# 05_-_MSP430F5529.net
KiCad netlist of a schematic drawn in Altium Designer
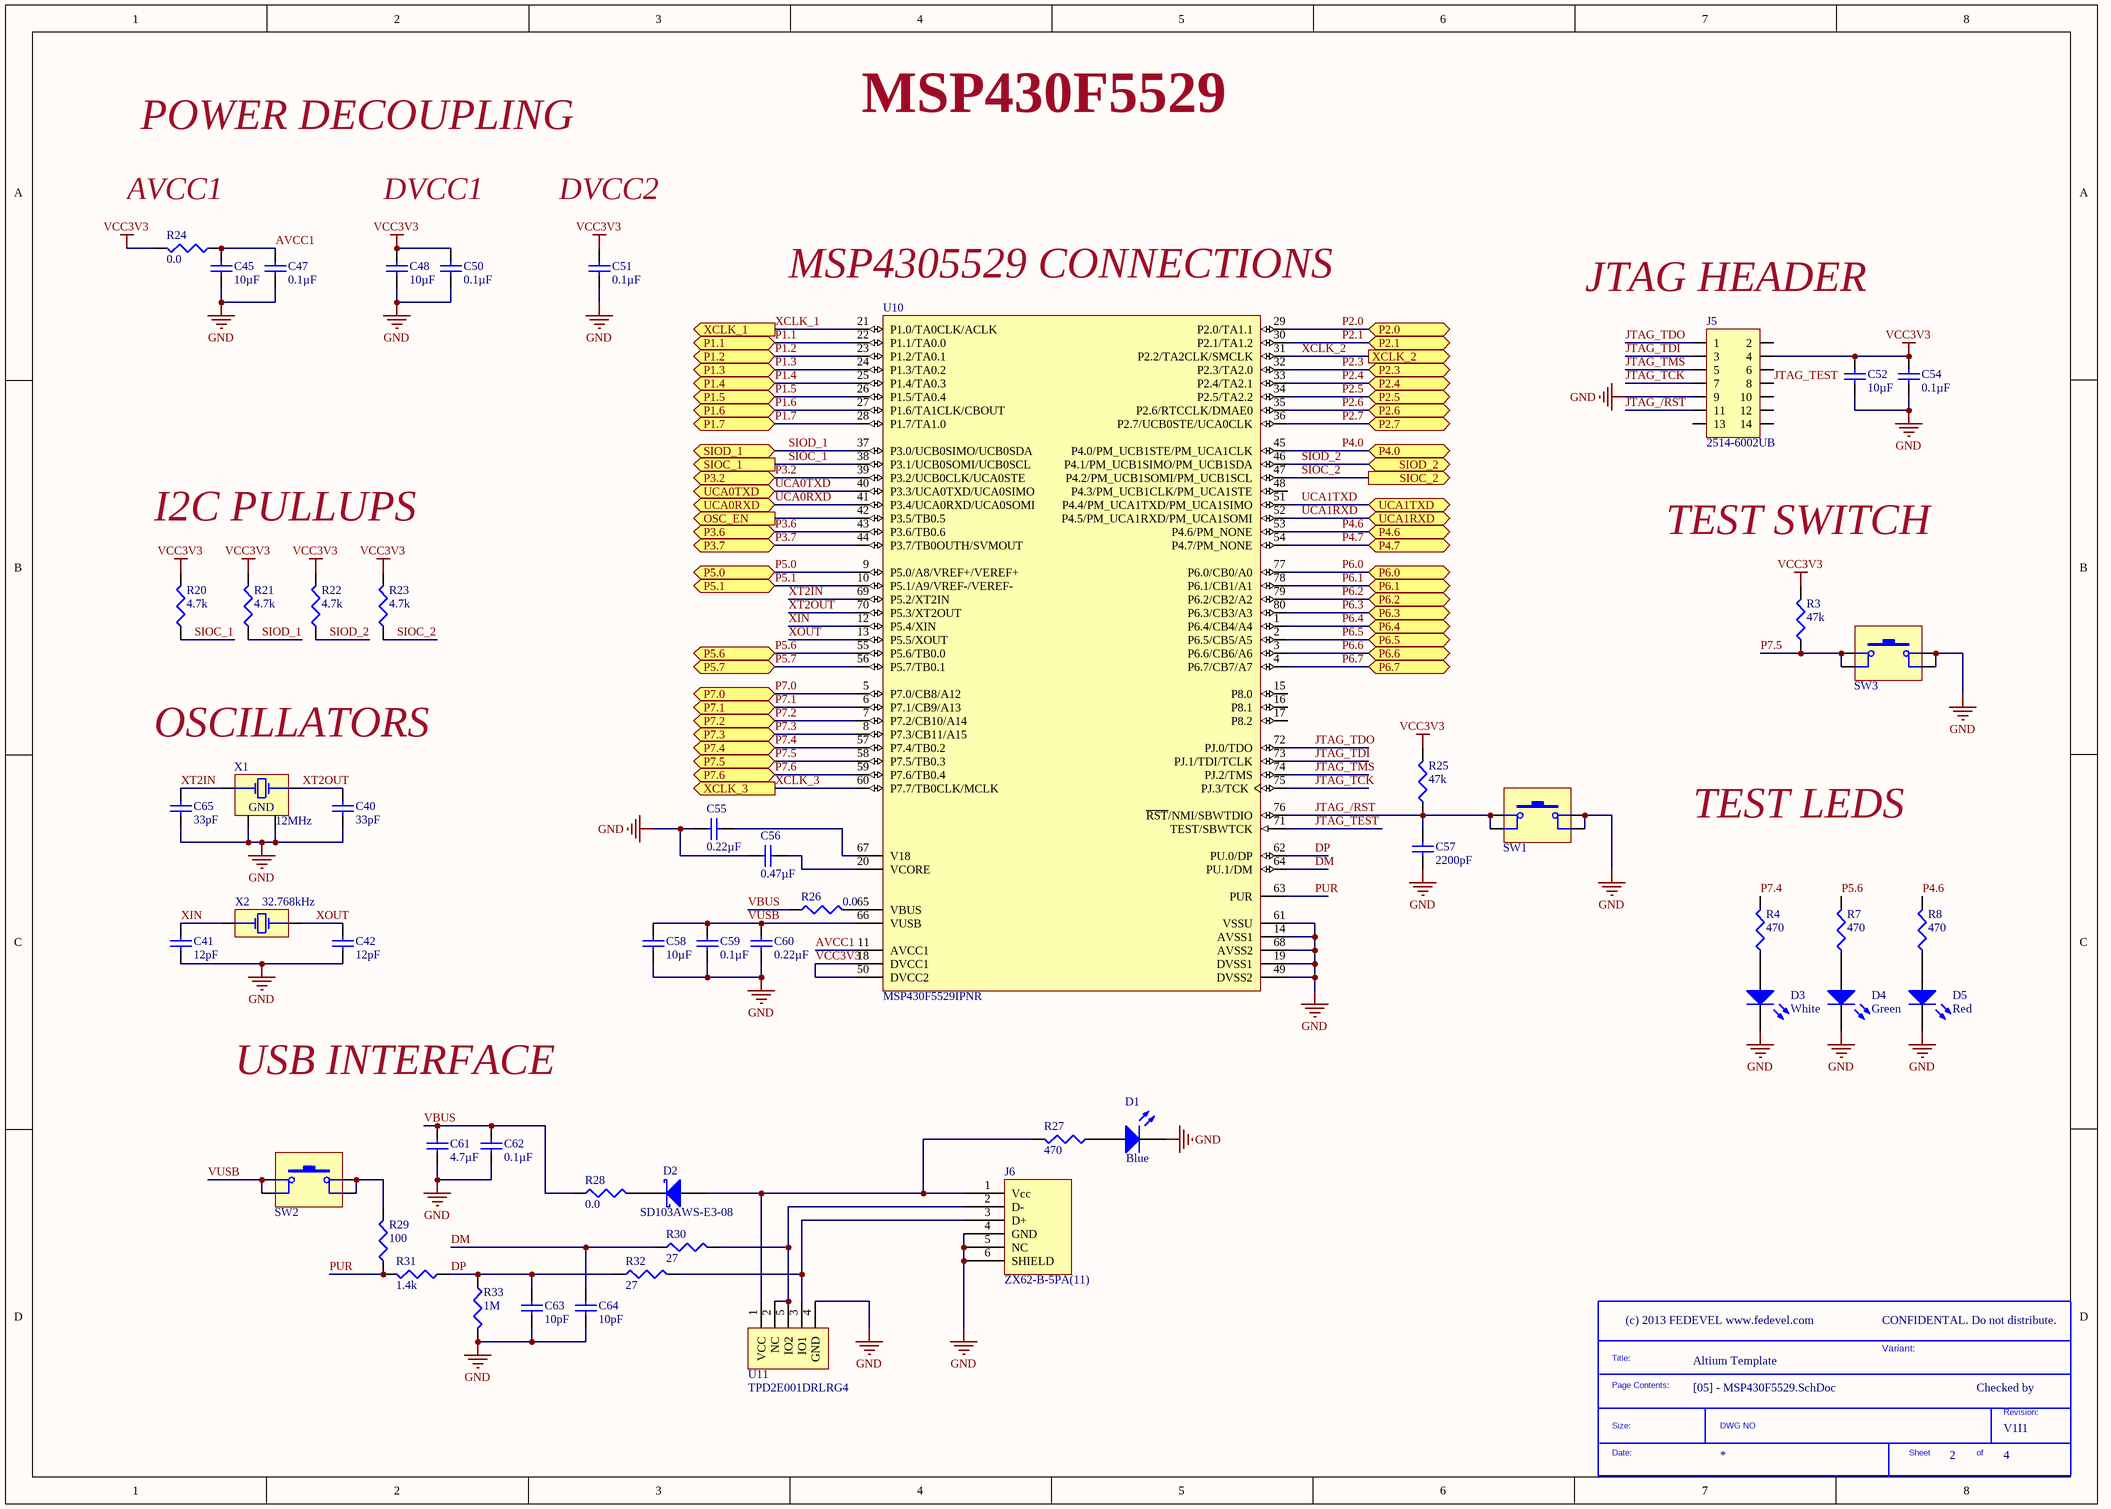
[diagram p0: [05] - MSP430F5529.SchDoc]

(export (version "E")
  (design (tool "Eeschema 10.0.6"))
  (components
    (comp (ref "C40")
      (value "C1608C0G1H330J080AA")
      (footprint "CAP-0603")
      (description "CAP CER 33PF 50V C0G 0603")
      (fields
        (field (name "MANUFACTURER") "TDK Corporation")
        (field (name "TOLERANCE") "±5%")
        (field (name "CAPACITANCE") "33pF")
      )
      (libsource (lib "camera_module") (part "C1608C0G1H330J080AA"))
    )
    (comp (ref "C41")
      (value "C1608C0G1H120J080AA")
      (footprint "CAP-0603")
      (description "CAP CER 12PF 50V C0G 0603")
      (fields
        (field (name "MANUFACTURER") "TDK Corporation")
        (field (name "TOLERANCE") "±5%")
        (field (name "CAPACITANCE") "12pF")
      )
      (libsource (lib "camera_module") (part "C1608C0G1H120J080AA"))
    )
    (comp (ref "C42")
      (value "C1608C0G1H120J080AA")
      (footprint "CAP-0603")
      (description "CAP CER 12PF 50V C0G 0603")
      (fields
        (field (name "MANUFACTURER") "TDK Corporation")
        (field (name "TOLERANCE") "±5%")
        (field (name "CAPACITANCE") "12pF")
      )
      (libsource (lib "camera_module") (part "C1608C0G1H120J080AA"))
    )
    (comp (ref "C45")
      (value "GRM21BR61E106KA73L")
      (footprint "CAP-0805")
      (description "CAP CER 10UF 25V X5R 0805")
      (fields
        (field (name "MANUFACTURER") "Murata Electronics North America")
        (field (name "TOLERANCE") "±10%")
        (field (name "CAPACITANCE") "10µF")
      )
      (libsource (lib "camera_module") (part "GRM21BR61E106KA73L"))
    )
    (comp (ref "C47")
      (value "GRM188R71C104KA01D")
      (footprint "CAP-0603")
      (description "CAP CER 0.1UF 16V X7R 0603")
      (fields
        (field (name "MANUFACTURER") "Murata Electronics North America")
        (field (name "TOLERANCE") "±10%")
        (field (name "CAPACITANCE") "0.1µF")
      )
      (libsource (lib "camera_module") (part "GRM188R71C104KA01D"))
    )
    (comp (ref "C48")
      (value "GRM21BR61E106KA73L")
      (footprint "CAP-0805")
      (description "CAP CER 10UF 25V X5R 0805")
      (fields
        (field (name "MANUFACTURER") "Murata Electronics North America")
        (field (name "TOLERANCE") "±10%")
        (field (name "CAPACITANCE") "10µF")
      )
      (libsource (lib "camera_module") (part "GRM21BR61E106KA73L"))
    )
    (comp (ref "C50")
      (value "GRM188R71C104KA01D")
      (footprint "CAP-0603")
      (description "CAP CER 0.1UF 16V X7R 0603")
      (fields
        (field (name "MANUFACTURER") "Murata Electronics North America")
        (field (name "TOLERANCE") "±10%")
        (field (name "CAPACITANCE") "0.1µF")
      )
      (libsource (lib "camera_module") (part "GRM188R71C104KA01D"))
    )
    (comp (ref "C51")
      (value "GRM188R71C104KA01D")
      (footprint "CAP-0603")
      (description "CAP CER 0.1UF 16V X7R 0603")
      (fields
        (field (name "MANUFACTURER") "Murata Electronics North America")
        (field (name "TOLERANCE") "±10%")
        (field (name "CAPACITANCE") "0.1µF")
      )
      (libsource (lib "camera_module") (part "GRM188R71C104KA01D"))
    )
    (comp (ref "C52")
      (value "GRM21BR61E106KA73L")
      (footprint "CAP-0805")
      (description "CAP CER 10UF 25V X5R 0805")
      (fields
        (field (name "MANUFACTURER") "Murata Electronics North America")
        (field (name "TOLERANCE") "±10%")
        (field (name "CAPACITANCE") "10µF")
      )
      (libsource (lib "camera_module") (part "GRM21BR61E106KA73L"))
    )
    (comp (ref "C54")
      (value "GRM188R71C104KA01D")
      (footprint "CAP-0603")
      (description "CAP CER 0.1UF 16V X7R 0603")
      (fields
        (field (name "MANUFACTURER") "Murata Electronics North America")
        (field (name "TOLERANCE") "±10%")
        (field (name "CAPACITANCE") "0.1µF")
      )
      (libsource (lib "camera_module") (part "GRM188R71C104KA01D"))
    )
    (comp (ref "C55")
      (value "GRM188R71C224KA01D")
      (footprint "CAP-0603")
      (description "CAP CER 0.22UF 16V X7R 0603")
      (fields
        (field (name "MANUFACTURER") "Murata Electronics North America")
        (field (name "TOLERANCE") "±10%")
        (field (name "CAPACITANCE") "0.22µF")
      )
      (libsource (lib "camera_module") (part "GRM188R71C224KA01D"))
    )
    (comp (ref "C56")
      (value "C1608X5R1C474K080AA")
      (footprint "CAP-0603")
      (description "CAP CER 0.47UF 16V X5R 0603")
      (fields
        (field (name "MANUFACTURER") "TDK Corporation")
        (field (name "TOLERANCE") "±10%")
        (field (name "CAPACITANCE") "0.47µF")
      )
      (libsource (lib "camera_module") (part "C1608X5R1C474K080AA"))
    )
    (comp (ref "C57")
      (value "GRM188R71C222KA01D")
      (footprint "CAP-0603")
      (description "CAP CER 2200PF 16V X7R 0603")
      (fields
        (field (name "MANUFACTURER") "Murata Electronics North America")
        (field (name "TOLERANCE") "±10%")
        (field (name "CAPACITANCE") "2200pF")
      )
      (libsource (lib "camera_module") (part "GRM188R71C222KA01D"))
    )
    (comp (ref "C58")
      (value "GRM21BR61E106KA73L")
      (footprint "CAP-0805")
      (description "CAP CER 10UF 25V X5R 0805")
      (fields
        (field (name "MANUFACTURER") "Murata Electronics North America")
        (field (name "TOLERANCE") "±10%")
        (field (name "CAPACITANCE") "10µF")
      )
      (libsource (lib "camera_module") (part "GRM21BR61E106KA73L"))
    )
    (comp (ref "C59")
      (value "GRM188R71C104KA01D")
      (footprint "CAP-0603")
      (description "CAP CER 0.1UF 16V X7R 0603")
      (fields
        (field (name "MANUFACTURER") "Murata Electronics North America")
        (field (name "TOLERANCE") "±10%")
        (field (name "CAPACITANCE") "0.1µF")
      )
      (libsource (lib "camera_module") (part "GRM188R71C104KA01D"))
    )
    (comp (ref "C60")
      (value "GRM188R71C224KA01D")
      (footprint "CAP-0603")
      (description "CAP CER 0.22UF 16V X7R 0603")
      (fields
        (field (name "MANUFACTURER") "Murata Electronics North America")
        (field (name "TOLERANCE") "±10%")
        (field (name "CAPACITANCE") "0.22µF")
      )
      (libsource (lib "camera_module") (part "GRM188R71C224KA01D"))
    )
    (comp (ref "C61")
      (value "GRM188R60J475KE19D")
      (footprint "CAP-0603")
      (description "CAP CER 4.7UF 6.3V X5R 0603")
      (fields
        (field (name "MANUFACTURER") "Murata Electronics North America")
        (field (name "TOLERANCE") "±10%")
        (field (name "CAPACITANCE") "4.7µF")
      )
      (libsource (lib "camera_module") (part "GRM188R60J475KE19D"))
    )
    (comp (ref "C62")
      (value "GRM188R71C104KA01D")
      (footprint "CAP-0603")
      (description "CAP CER 0.1UF 16V X7R 0603")
      (fields
        (field (name "MANUFACTURER") "Murata Electronics North America")
        (field (name "TOLERANCE") "±10%")
        (field (name "CAPACITANCE") "0.1µF")
      )
      (libsource (lib "camera_module") (part "GRM188R71C104KA01D"))
    )
    (comp (ref "C63")
      (value "GRM1885C1H100JA01D")
      (footprint "CAP-0603")
      (description "CAP CER 10PF 50V NP0 0603")
      (fields
        (field (name "MANUFACTURER") "Murata Electronics North America")
        (field (name "TOLERANCE") "±5%")
        (field (name "CAPACITANCE") "10pF")
      )
      (libsource (lib "camera_module") (part "GRM1885C1H100JA01D"))
    )
    (comp (ref "C64")
      (value "GRM1885C1H100JA01D")
      (footprint "CAP-0603")
      (description "CAP CER 10PF 50V NP0 0603")
      (fields
        (field (name "MANUFACTURER") "Murata Electronics North America")
        (field (name "TOLERANCE") "±5%")
        (field (name "CAPACITANCE") "10pF")
      )
      (libsource (lib "camera_module") (part "GRM1885C1H100JA01D"))
    )
    (comp (ref "C65")
      (value "C1608C0G1H330J080AA")
      (footprint "CAP-0603")
      (description "CAP CER 33PF 50V C0G 0603")
      (fields
        (field (name "MANUFACTURER") "TDK Corporation")
        (field (name "TOLERANCE") "±5%")
        (field (name "CAPACITANCE") "33pF")
      )
      (libsource (lib "camera_module") (part "C1608C0G1H330J080AA"))
    )
    (comp (ref "D1")
      (value "LB Q39E-N1OO-35-1")
      (footprint "LED_0603")
      (description "LED BLUE DIFFUSED 0603 SMD")
      (fields (field (name "MANUFACTURER") "OSRAM Opto Semiconductors Inc.") (field (name "COLOR") "Blue"))
      (libsource (lib "camera_module") (part "LB Q39E-N1OO-35-1"))
    )
    (comp (ref "D2")
      (value "SD103AWS-E3-08")
      (footprint "SOD-323")
      (description "DIODE SCHOTTKY 40V 350MA SOD323")
      (fields (field (name "MANUFACTURER") "Vishay Semiconductor Diodes Division"))
      (libsource (lib "camera_module") (part "SD103AWS-E3-08"))
    )
    (comp (ref "D3")
      (value "SMLE12WBC7W1")
      (footprint "LED_0603")
      (description "LED WHITE DIFFUSED 0603 SMD")
      (fields (field (name "MANUFACTURER") "Rohm Semiconductor") (field (name "COLOR") "White"))
      (libsource (lib "camera_module") (part "SMLE12WBC7W1"))
    )
    (comp (ref "D4")
      (value "SML-D12M8WT86")
      (footprint "LED_0603")
      (description "LED GREEN DIFFUSED 0603 SMD")
      (fields (field (name "MANUFACTURER") "Rohm Semiconductor") (field (name "COLOR") "Green"))
      (libsource (lib "camera_module") (part "SML-D12M8WT86"))
    )
    (comp (ref "D5")
      (value "SML-D12U8WT86")
      (footprint "LED_0603")
      (description "LED RED DIFFUSED 0603 SMD")
      (fields (field (name "MANUFACTURER") "Rohm Semiconductor") (field (name "COLOR") "Red"))
      (libsource (lib "camera_module") (part "SML-D12U8WT86"))
    )
    (comp (ref "J5")
      (value "2514-6002UB")
      (footprint "2514-6002UB")
      (description "SHROUDED HEADER 14 POS STRAIGHT")
      (fields (field (name "MANUFACTURER") "3M"))
      (libsource (lib "camera_module") (part "2514-6002UB"))
    )
    (comp (ref "J6")
      (value "ZX62-B-5PA(11)")
      (footprint "micro-USB")
      (description "CONN RCPT MICRO USB B SMD R/A")
      (fields (field (name "MANUFACTURER") "Hirose Electric Co Ltd"))
      (libsource (lib "camera_module") (part "ZX62-B-5PA(11)"))
    )
    (comp (ref "R3")
      (value "Panasonic Electronic Components")
      (footprint "CAP-0603")
      (description "RES SMD 47K OHM 1% 1/10W 0603")
      (fields
        (field (name "MANUFACTURER PART NUMBER") "ERJ-3EKF4702V")
        (field (name "TOLERANCE") "±1%")
        (field (name "RESISTANCE (OHMS)") "47k")
      )
      (libsource (lib "camera_module") (part "ERJ-3EKF4702V"))
    )
    (comp (ref "R4")
      (value "ERJ-3EKF4700V")
      (footprint "R0603")
      (description "RES SMD 470 OHM 1% 1/10W 0603")
      (fields
        (field (name "MANUFACTURER") "Panasonic Electronic Components")
        (field (name "TOLERANCE") "±1%")
        (field (name "RESISTANCE (OHMS)") "470")
      )
      (libsource (lib "camera_module") (part "ERJ-3EKF4700V"))
    )
    (comp (ref "R7")
      (value "ERJ-3EKF4700V")
      (footprint "R0603")
      (description "RES SMD 470 OHM 1% 1/10W 0603")
      (fields
        (field (name "MANUFACTURER") "Panasonic Electronic Components")
        (field (name "TOLERANCE") "±1%")
        (field (name "RESISTANCE (OHMS)") "470")
      )
      (libsource (lib "camera_module") (part "ERJ-3EKF4700V"))
    )
    (comp (ref "R8")
      (value "ERJ-3EKF4700V")
      (footprint "R0603")
      (description "RES SMD 470 OHM 1% 1/10W 0603")
      (fields
        (field (name "MANUFACTURER") "Panasonic Electronic Components")
        (field (name "TOLERANCE") "±1%")
        (field (name "RESISTANCE (OHMS)") "470")
      )
      (libsource (lib "camera_module") (part "ERJ-3EKF4700V"))
    )
    (comp (ref "R20")
      (value "ERJ-3EKF4701V")
      (footprint "R0603")
      (description "RES SMD 4.7K OHM 1% 1/10W 0603")
      (fields
        (field (name "MANUFACTURER") "Panasonic Electronic Components")
        (field (name "TOLERANCE") "±1%")
        (field (name "RESISTANCE (OHMS)") "4.7k")
      )
      (libsource (lib "camera_module") (part "ERJ-3EKF4701V"))
    )
    (comp (ref "R21")
      (value "ERJ-3EKF4701V")
      (footprint "R0603")
      (description "RES SMD 4.7K OHM 1% 1/10W 0603")
      (fields
        (field (name "MANUFACTURER") "Panasonic Electronic Components")
        (field (name "TOLERANCE") "±1%")
        (field (name "RESISTANCE (OHMS)") "4.7k")
      )
      (libsource (lib "camera_module") (part "ERJ-3EKF4701V"))
    )
    (comp (ref "R22")
      (value "ERJ-3EKF4701V")
      (footprint "R0603")
      (description "RES SMD 4.7K OHM 1% 1/10W 0603")
      (fields
        (field (name "MANUFACTURER") "Panasonic Electronic Components")
        (field (name "TOLERANCE") "±1%")
        (field (name "RESISTANCE (OHMS)") "4.7k")
      )
      (libsource (lib "camera_module") (part "ERJ-3EKF4701V"))
    )
    (comp (ref "R23")
      (value "ERJ-3EKF4701V")
      (footprint "R0603")
      (description "RES SMD 4.7K OHM 1% 1/10W 0603")
      (fields
        (field (name "MANUFACTURER") "Panasonic Electronic Components")
        (field (name "TOLERANCE") "±1%")
        (field (name "RESISTANCE (OHMS)") "4.7k")
      )
      (libsource (lib "camera_module") (part "ERJ-3EKF4701V"))
    )
    (comp (ref "R24")
      (value "ERJ-3GEY0R00V")
      (footprint "R0603")
      (description "RES SMD 0.0OHM JUMPER 1/10W 0603")
      (fields
        (field (name "MANUFACTURER") "Panasonic Electronic Components")
        (field (name "TOLERANCE") "Jumper")
        (field (name "RESISTANCE (OHMS)") "0.0")
      )
      (libsource (lib "camera_module") (part "ERJ-3GEY0R00V"))
    )
    (comp (ref "R25")
      (value "Panasonic Electronic Components")
      (footprint "CAP-0603")
      (description "RES SMD 47K OHM 1% 1/10W 0603")
      (fields
        (field (name "MANUFACTURER PART NUMBER") "ERJ-3EKF4702V")
        (field (name "TOLERANCE") "±1%")
        (field (name "RESISTANCE (OHMS)") "47k")
      )
      (libsource (lib "camera_module") (part "ERJ-3EKF4702V"))
    )
    (comp (ref "R26")
      (value "ERJ-3GEY0R00V")
      (footprint "R0603")
      (description "RES SMD 0.0OHM JUMPER 1/10W 0603")
      (fields
        (field (name "MANUFACTURER") "Panasonic Electronic Components")
        (field (name "TOLERANCE") "Jumper")
        (field (name "RESISTANCE (OHMS)") "0.0")
      )
      (libsource (lib "camera_module") (part "ERJ-3GEY0R00V"))
    )
    (comp (ref "R27")
      (value "ERJ-3EKF4700V")
      (footprint "R0603")
      (description "RES SMD 470 OHM 1% 1/10W 0603")
      (fields
        (field (name "MANUFACTURER") "Panasonic Electronic Components")
        (field (name "TOLERANCE") "±1%")
        (field (name "RESISTANCE (OHMS)") "470")
      )
      (libsource (lib "camera_module") (part "ERJ-3EKF4700V"))
    )
    (comp (ref "R28")
      (value "ERJ-3GEY0R00V")
      (footprint "R0603")
      (description "RES SMD 0.0OHM JUMPER 1/10W 0603")
      (fields
        (field (name "MANUFACTURER") "Panasonic Electronic Components")
        (field (name "TOLERANCE") "Jumper")
        (field (name "RESISTANCE (OHMS)") "0.0")
      )
      (libsource (lib "camera_module") (part "ERJ-3GEY0R00V"))
    )
    (comp (ref "R29")
      (value "ERJ-3EKF1000V")
      (footprint "R0603")
      (description "RES SMD 100 OHM 1% 1/10W 0603")
      (fields
        (field (name "MANUFACTURER") "Panasonic Electronic Components")
        (field (name "TOLERANCE") "±1%")
        (field (name "RESISTANCE (OHMS)") "100")
      )
      (libsource (lib "camera_module") (part "ERJ-3EKF1000V"))
    )
    (comp (ref "R30")
      (value "ERJ-3EKF27R0V")
      (footprint "R0603")
      (description "RES SMD 27 OHM 1% 1/10W 0603")
      (fields
        (field (name "MANUFACTURER") "Panasonic Electronic Components")
        (field (name "TOLERANCE") "±1%")
        (field (name "RESISTANCE (OHMS)") "27")
      )
      (libsource (lib "camera_module") (part "ERJ-3EKF27R0V"))
    )
    (comp (ref "R31")
      (value "ERJ-3EKF1401V")
      (footprint "R0603")
      (description "RES SMD 1.4K OHM 1% 1/10W 0603")
      (fields
        (field (name "MANUFACTURER") "Panasonic Electronic Components")
        (field (name "TOLERANCE") "±1%")
        (field (name "RESISTANCE (OHMS)") "1.4k")
      )
      (libsource (lib "camera_module") (part "ERJ-3EKF1401V"))
    )
    (comp (ref "R32")
      (value "ERJ-3EKF27R0V")
      (footprint "R0603")
      (description "RES SMD 27 OHM 1% 1/10W 0603")
      (fields
        (field (name "MANUFACTURER") "Panasonic Electronic Components")
        (field (name "TOLERANCE") "±1%")
        (field (name "RESISTANCE (OHMS)") "27")
      )
      (libsource (lib "camera_module") (part "ERJ-3EKF27R0V"))
    )
    (comp (ref "R33")
      (value "ERJ-3EKF1004V")
      (footprint "R0603")
      (description "RES SMD 1M OHM 1% 1/10W 0603")
      (fields
        (field (name "MANUFACTURER") "Panasonic Electronic Components")
        (field (name "TOLERANCE") "±1%")
        (field (name "RESISTANCE (OHMS)") "1M")
      )
      (libsource (lib "camera_module") (part "ERJ-3EKF1004V"))
    )
    (comp (ref "SW1")
      (value "PTS645SH50SMTR92 LFS")
      (footprint "Tactile Switch")
      (description "SWITCH TACTILE SPST-NO 0.05A 12V")
      (fields (field (name "MANUFACTURER") "C&K Components"))
      (libsource (lib "camera_module") (part "PTS645SH50SMTR92 LFS"))
    )
    (comp (ref "SW2")
      (value "PTS645SH50SMTR92 LFS")
      (footprint "Tactile Switch")
      (description "SWITCH TACTILE SPST-NO 0.05A 12V")
      (fields (field (name "MANUFACTURER") "C&K Components"))
      (libsource (lib "camera_module") (part "PTS645SH50SMTR92 LFS"))
    )
    (comp (ref "SW3")
      (value "PTS645SH50SMTR92 LFS")
      (footprint "Tactile Switch")
      (description "SWITCH TACTILE SPST-NO 0.05A 12V")
      (fields (field (name "MANUFACTURER") "C&K Components"))
      (libsource (lib "camera_module") (part "PTS645SH50SMTR92 LFS"))
    )
    (comp (ref "U10")
      (value "MSP430F5529IPNR")
      (footprint "TI-PN80_N")
      (description "IC MCU 16BIT 128KB FLASH 80LQFP")
      (fields (field (name "MANUFACTURER") "Texas Instruments"))
      (libsource (lib "camera_module") (part "MSP430F5529IPNR"))
    )
    (comp (ref "U11")
      (value "TPD2E001DRLRG4")
      (footprint "DRL")
      (description "TVS DIODE 5.5VWM 100VC SOT5")
      (fields (field (name "MANUFACTURER") "Texas Instruments"))
      (libsource (lib "camera_module") (part "TPD2E001DRLRG4"))
    )
    (comp (ref "X1")
      (value "12MHz")
      (footprint "XTAL-4SMD 5x3.20")
      (description "CRYSTAL 12.0000MHZ 20PF SMD")
      (fields
        (field (name "MANUFACTURER") "ECS Inc.")
        (field (name "MANUFACTURER PART NUMBER") "ECS-120-20-30B-TR")
      )
      (libsource (lib "camera_module") (part "ECS-120-20-30B-TR"))
    )
    (comp (ref "X2")
      (value "32.768kHz")
      (footprint "2-SMD_xtal")
      (description "CRYSTAL 32.7680KHZ 9PF SMD")
      (fields
        (field (name "MANUFACTURER") "Abracon LLC")
        (field (name "MANUFACTURER PART NUMBER") "ABS07-32.768KHZ-9-T")
      )
      (libsource (lib "camera_module") (part "ABS07-32.768KHZ-9-T"))
    )
  )
  (nets
    (net (code "1") (name "/AVCC1") (class "Default")
      (node (ref "C45") (pin "1") (pinfunction "1_1") (pintype "passive"))
      (node (ref "C47") (pin "1") (pinfunction "1_1") (pintype "passive"))
      (node (ref "R24") (pin "1") (pinfunction "1_1") (pintype "passive"))
      (node (ref "U10") (pin "11") (pinfunction "AVCC1_11") (pintype "power_in"))
    )
    (net (code "2") (name "/DM") (class "Default")
      (node (ref "C64") (pin "1") (pinfunction "1_1") (pintype "passive"))
      (node (ref "R30") (pin "1") (pinfunction "1_1") (pintype "passive"))
      (node (ref "U10") (pin "64") (pinfunction "PU.1/DM_64") (pintype "bidirectional"))
    )
    (net (code "3") (name "/DP") (class "Default")
      (node (ref "C63") (pin "1") (pinfunction "1_1") (pintype "passive"))
      (node (ref "R31") (pin "1") (pinfunction "1_1") (pintype "passive"))
      (node (ref "R32") (pin "1") (pinfunction "1_1") (pintype "passive"))
      (node (ref "R33") (pin "1") (pinfunction "1_1") (pintype "passive"))
      (node (ref "U10") (pin "62") (pinfunction "PU.0/DP_62") (pintype "bidirectional"))
    )
    (net (code "4") (name "/JTAG_TCK") (class "Default")
      (node (ref "J5") (pin "7") (pinfunction "7_7") (pintype "passive"))
      (node (ref "U10") (pin "75") (pinfunction "PJ.3/TCK_75") (pintype "bidirectional"))
    )
    (net (code "5") (name "/JTAG_TDI") (class "Default")
      (node (ref "J5") (pin "3") (pinfunction "3_3") (pintype "passive"))
      (node (ref "U10") (pin "73") (pinfunction "PJ.1/TDI/TCLK_73") (pintype "bidirectional"))
    )
    (net (code "6") (name "/JTAG_TDO") (class "Default")
      (node (ref "J5") (pin "1") (pinfunction "1_1") (pintype "passive"))
      (node (ref "U10") (pin "72") (pinfunction "PJ.0/TDO_72") (pintype "bidirectional"))
    )
    (net (code "7") (name "/JTAG_TEST") (class "Default")
      (node (ref "J5") (pin "8") (pinfunction "8_8") (pintype "passive"))
      (node (ref "U10") (pin "71") (pinfunction "TEST/SBWTCK_71") (pintype "input"))
    )
    (net (code "8") (name "/JTAG_TMS") (class "Default")
      (node (ref "J5") (pin "5") (pinfunction "5_5") (pintype "passive"))
      (node (ref "U10") (pin "74") (pinfunction "PJ.2/TMS_74") (pintype "bidirectional"))
    )
    (net (code "9") (name "/JTAG_{slash}RST") (class "Default")
      (node (ref "C57") (pin "1") (pinfunction "1_1") (pintype "passive"))
      (node (ref "J5") (pin "11") (pinfunction "11_11") (pintype "passive"))
      (node (ref "R25") (pin "1") (pinfunction "1_1") (pintype "passive"))
      (node (ref "SW1") (pin "1") (pinfunction "1_1") (pintype "passive"))
      (node (ref "SW1") (pin "2") (pinfunction "2_2") (pintype "passive"))
      (node (ref "U10") (pin "76") (pinfunction "~{RST}/NMI/SBWTDIO_76") (pintype "bidirectional"))
    )
    (net (code "10") (name "/OSC_EN") (class "Default")
      (node (ref "U10") (pin "42") (pinfunction "P3.5/TB0.5_42") (pintype "bidirectional"))
    )
    (net (code "11") (name "/P1.1") (class "Default")
      (node (ref "U10") (pin "22") (pinfunction "P1.1/TA0.0_22") (pintype "bidirectional"))
    )
    (net (code "12") (name "/P1.2") (class "Default")
      (node (ref "U10") (pin "23") (pinfunction "P1.2/TA0.1_23") (pintype "bidirectional"))
    )
    (net (code "13") (name "/P1.3") (class "Default")
      (node (ref "U10") (pin "24") (pinfunction "P1.3/TA0.2_24") (pintype "bidirectional"))
    )
    (net (code "14") (name "/P1.4") (class "Default")
      (node (ref "U10") (pin "25") (pinfunction "P1.4/TA0.3_25") (pintype "bidirectional"))
    )
    (net (code "15") (name "/P1.5") (class "Default")
      (node (ref "U10") (pin "26") (pinfunction "P1.5/TA0.4_26") (pintype "bidirectional"))
    )
    (net (code "16") (name "/P1.6") (class "Default")
      (node (ref "U10") (pin "27") (pinfunction "P1.6/TA1CLK/CBOUT_27") (pintype "bidirectional"))
    )
    (net (code "17") (name "/P1.7") (class "Default")
      (node (ref "U10") (pin "28") (pinfunction "P1.7/TA1.0_28") (pintype "bidirectional"))
    )
    (net (code "18") (name "/P2.0") (class "Default")
      (node (ref "U10") (pin "29") (pinfunction "P2.0/TA1.1_29") (pintype "bidirectional"))
    )
    (net (code "19") (name "/P2.1") (class "Default")
      (node (ref "U10") (pin "30") (pinfunction "P2.1/TA1.2_30") (pintype "bidirectional"))
    )
    (net (code "20") (name "/P2.3") (class "Default")
      (node (ref "U10") (pin "32") (pinfunction "P2.3/TA2.0_32") (pintype "bidirectional"))
    )
    (net (code "21") (name "/P2.4") (class "Default")
      (node (ref "U10") (pin "33") (pinfunction "P2.4/TA2.1_33") (pintype "bidirectional"))
    )
    (net (code "22") (name "/P2.5") (class "Default")
      (node (ref "U10") (pin "34") (pinfunction "P2.5/TA2.2_34") (pintype "bidirectional"))
    )
    (net (code "23") (name "/P2.6") (class "Default")
      (node (ref "U10") (pin "35") (pinfunction "P2.6/RTCCLK/DMAE0_35") (pintype "bidirectional"))
    )
    (net (code "24") (name "/P2.7") (class "Default")
      (node (ref "U10") (pin "36") (pinfunction "P2.7/UCB0STE/UCA0CLK_36") (pintype "bidirectional"))
    )
    (net (code "25") (name "/P3.2") (class "Default")
      (node (ref "U10") (pin "39") (pinfunction "P3.2/UCB0CLK/UCA0STE_39") (pintype "bidirectional"))
    )
    (net (code "26") (name "/P3.6") (class "Default")
      (node (ref "U10") (pin "43") (pinfunction "P3.6/TB0.6_43") (pintype "bidirectional"))
    )
    (net (code "27") (name "/P3.7") (class "Default")
      (node (ref "U10") (pin "44") (pinfunction "P3.7/TB0OUTH/SVMOUT_44") (pintype "bidirectional"))
    )
    (net (code "28") (name "/P4.0") (class "Default")
      (node (ref "U10") (pin "45") (pinfunction "P4.0/PM_UCB1STE/PM_UCA1CLK_45") (pintype "bidirectional"))
    )
    (net (code "29") (name "/P4.6") (class "Default")
      (node (ref "R8") (pin "2") (pinfunction "2_2") (pintype "passive"))
      (node (ref "U10") (pin "53") (pinfunction "P4.6/PM_NONE_53") (pintype "bidirectional"))
    )
    (net (code "30") (name "/P4.7") (class "Default")
      (node (ref "U10") (pin "54") (pinfunction "P4.7/PM_NONE_54") (pintype "bidirectional"))
    )
    (net (code "31") (name "/P5.0") (class "Default")
      (node (ref "U10") (pin "9") (pinfunction "P5.0/A8/VREF+/VEREF+_9") (pintype "bidirectional"))
    )
    (net (code "32") (name "/P5.1") (class "Default")
      (node (ref "U10") (pin "10") (pinfunction "P5.1/A9/VREF-/VEREF-_10") (pintype "bidirectional"))
    )
    (net (code "33") (name "/P5.6") (class "Default")
      (node (ref "R7") (pin "2") (pinfunction "2_2") (pintype "passive"))
      (node (ref "U10") (pin "55") (pinfunction "P5.6/TB0.0_55") (pintype "bidirectional"))
    )
    (net (code "34") (name "/P5.7") (class "Default")
      (node (ref "U10") (pin "56") (pinfunction "P5.7/TB0.1_56") (pintype "bidirectional"))
    )
    (net (code "35") (name "/P6.0") (class "Default")
      (node (ref "U10") (pin "77") (pinfunction "P6.0/CB0/A0_77") (pintype "bidirectional"))
    )
    (net (code "36") (name "/P6.1") (class "Default")
      (node (ref "U10") (pin "78") (pinfunction "P6.1/CB1/A1_78") (pintype "bidirectional"))
    )
    (net (code "37") (name "/P6.2") (class "Default")
      (node (ref "U10") (pin "79") (pinfunction "P6.2/CB2/A2_79") (pintype "bidirectional"))
    )
    (net (code "38") (name "/P6.3") (class "Default")
      (node (ref "U10") (pin "80") (pinfunction "P6.3/CB3/A3_80") (pintype "bidirectional"))
    )
    (net (code "39") (name "/P6.4") (class "Default")
      (node (ref "U10") (pin "1") (pinfunction "P6.4/CB4/A4_1") (pintype "bidirectional"))
    )
    (net (code "40") (name "/P6.5") (class "Default")
      (node (ref "U10") (pin "2") (pinfunction "P6.5/CB5/A5_2") (pintype "bidirectional"))
    )
    (net (code "41") (name "/P6.6") (class "Default")
      (node (ref "U10") (pin "3") (pinfunction "P6.6/CB6/A6_3") (pintype "bidirectional"))
    )
    (net (code "42") (name "/P6.7") (class "Default")
      (node (ref "U10") (pin "4") (pinfunction "P6.7/CB7/A7_4") (pintype "bidirectional"))
    )
    (net (code "43") (name "/P7.0") (class "Default")
      (node (ref "U10") (pin "5") (pinfunction "P7.0/CB8/A12_5") (pintype "bidirectional"))
    )
    (net (code "44") (name "/P7.1") (class "Default")
      (node (ref "U10") (pin "6") (pinfunction "P7.1/CB9/A13_6") (pintype "bidirectional"))
    )
    (net (code "45") (name "/P7.2") (class "Default")
      (node (ref "U10") (pin "7") (pinfunction "P7.2/CB10/A14_7") (pintype "bidirectional"))
    )
    (net (code "46") (name "/P7.3") (class "Default")
      (node (ref "U10") (pin "8") (pinfunction "P7.3/CB11/A15_8") (pintype "bidirectional"))
    )
    (net (code "47") (name "/P7.4") (class "Default")
      (node (ref "R4") (pin "2") (pinfunction "2_2") (pintype "passive"))
      (node (ref "U10") (pin "57") (pinfunction "P7.4/TB0.2_57") (pintype "bidirectional"))
    )
    (net (code "48") (name "/P7.5") (class "Default")
      (node (ref "R3") (pin "1") (pinfunction "1_1") (pintype "passive"))
      (node (ref "SW3") (pin "1") (pinfunction "1_1") (pintype "passive"))
      (node (ref "SW3") (pin "2") (pinfunction "2_2") (pintype "passive"))
      (node (ref "U10") (pin "58") (pinfunction "P7.5/TB0.3_58") (pintype "bidirectional"))
    )
    (net (code "49") (name "/P7.6") (class "Default")
      (node (ref "U10") (pin "59") (pinfunction "P7.6/TB0.4_59") (pintype "bidirectional"))
    )
    (net (code "50") (name "/PUR") (class "Default")
      (node (ref "R29") (pin "1") (pinfunction "1_1") (pintype "passive"))
      (node (ref "R31") (pin "2") (pinfunction "2_2") (pintype "passive"))
      (node (ref "U10") (pin "63") (pinfunction "PUR_63") (pintype "passive"))
    )
    (net (code "51") (name "/SIOC_1") (class "Default")
      (node (ref "R20") (pin "1") (pinfunction "1_1") (pintype "passive"))
      (node (ref "U10") (pin "38") (pinfunction "P3.1/UCB0SOMI/UCB0SCL_38") (pintype "bidirectional"))
    )
    (net (code "52") (name "/SIOC_2") (class "Default")
      (node (ref "R23") (pin "1") (pinfunction "1_1") (pintype "passive"))
      (node (ref "U10") (pin "47") (pinfunction "P4.2/PM_UCB1SOMI/PM_UCB1SCL_47") (pintype "bidirectional"))
    )
    (net (code "53") (name "/SIOD_1") (class "Default")
      (node (ref "R21") (pin "1") (pinfunction "1_1") (pintype "passive"))
      (node (ref "U10") (pin "37") (pinfunction "P3.0/UCB0SIMO/UCB0SDA_37") (pintype "bidirectional"))
    )
    (net (code "54") (name "/SIOD_2") (class "Default")
      (node (ref "R22") (pin "1") (pinfunction "1_1") (pintype "passive"))
      (node (ref "U10") (pin "46") (pinfunction "P4.1/PM_UCB1SIMO/PM_UCB1SDA_46") (pintype "bidirectional"))
    )
    (net (code "55") (name "/UCA0RXD") (class "Default")
      (node (ref "U10") (pin "41") (pinfunction "P3.4/UCA0RXD/UCA0SOMI_41") (pintype "bidirectional"))
    )
    (net (code "56") (name "/UCA0TXD") (class "Default")
      (node (ref "U10") (pin "40") (pinfunction "P3.3/UCA0TXD/UCA0SIMO_40") (pintype "bidirectional"))
    )
    (net (code "57") (name "/UCA1RXD") (class "Default")
      (node (ref "U10") (pin "52") (pinfunction "P4.5/PM_UCA1RXD/PM_UCA1SOMI_52") (pintype "bidirectional"))
    )
    (net (code "58") (name "/UCA1TXD") (class "Default")
      (node (ref "U10") (pin "51") (pinfunction "P4.4/PM_UCA1TXD/PM_UCA1SIMO_51") (pintype "bidirectional"))
    )
    (net (code "59") (name "/VBUS") (class "Default")
      (node (ref "C61") (pin "1") (pinfunction "1_1") (pintype "passive"))
      (node (ref "C62") (pin "1") (pinfunction "1_1") (pintype "passive"))
      (node (ref "R26") (pin "1") (pinfunction "1_1") (pintype "passive"))
      (node (ref "R28") (pin "1") (pinfunction "1_1") (pintype "passive"))
    )
    (net (code "60") (name "/VUSB") (class "Default")
      (node (ref "C58") (pin "2") (pinfunction "2_2") (pintype "passive"))
      (node (ref "C59") (pin "2") (pinfunction "2_2") (pintype "passive"))
      (node (ref "C60") (pin "1") (pinfunction "1_1") (pintype "passive"))
      (node (ref "SW2") (pin "1") (pinfunction "1_1") (pintype "passive"))
      (node (ref "SW2") (pin "2") (pinfunction "2_2") (pintype "passive"))
      (node (ref "U10") (pin "66") (pinfunction "VUSB_66") (pintype "power_in"))
    )
    (net (code "61") (name "/XCLK_1") (class "Default")
      (node (ref "U10") (pin "21") (pinfunction "P1.0/TA0CLK/ACLK_21") (pintype "bidirectional"))
    )
    (net (code "62") (name "/XCLK_2") (class "Default")
      (node (ref "U10") (pin "31") (pinfunction "P2.2/TA2CLK/SMCLK_31") (pintype "bidirectional"))
    )
    (net (code "63") (name "/XCLK_3") (class "Default")
      (node (ref "U10") (pin "60") (pinfunction "P7.7/TB0CLK/MCLK_60") (pintype "bidirectional"))
    )
    (net (code "64") (name "/XIN") (class "Default")
      (node (ref "C41") (pin "1") (pinfunction "1_1") (pintype "passive"))
      (node (ref "U10") (pin "12") (pinfunction "P5.4/XIN_12") (pintype "bidirectional"))
      (node (ref "X2") (pin "2") (pinfunction "OSC2_2") (pintype "passive"))
    )
    (net (code "65") (name "/XOUT") (class "Default")
      (node (ref "C42") (pin "1") (pinfunction "1_1") (pintype "passive"))
      (node (ref "U10") (pin "13") (pinfunction "P5.5/XOUT_13") (pintype "bidirectional"))
      (node (ref "X2") (pin "1") (pinfunction "OSC1_1") (pintype "passive"))
    )
    (net (code "66") (name "/XT2IN") (class "Default")
      (node (ref "C65") (pin "1") (pinfunction "1_1") (pintype "passive"))
      (node (ref "U10") (pin "69") (pinfunction "P5.2/XT2IN_69") (pintype "bidirectional"))
      (node (ref "X1") (pin "1") (pinfunction "OSC1_1") (pintype "passive"))
    )
    (net (code "67") (name "/XT2OUT") (class "Default")
      (node (ref "C40") (pin "1") (pinfunction "1_1") (pintype "passive"))
      (node (ref "U10") (pin "70") (pinfunction "P5.3/XT2OUT_70") (pintype "bidirectional"))
      (node (ref "X1") (pin "3") (pinfunction "OSC2_3") (pintype "passive"))
    )
    (net (code "68") (name "GND") (class "Default")
      (node (ref "C40") (pin "2") (pinfunction "2_2") (pintype "passive"))
      (node (ref "C41") (pin "2") (pinfunction "2_2") (pintype "passive"))
      (node (ref "C42") (pin "2") (pinfunction "2_2") (pintype "passive"))
      (node (ref "C45") (pin "2") (pinfunction "2_2") (pintype "passive"))
      (node (ref "C47") (pin "2") (pinfunction "2_2") (pintype "passive"))
      (node (ref "C48") (pin "2") (pinfunction "2_2") (pintype "passive"))
      (node (ref "C50") (pin "2") (pinfunction "2_2") (pintype "passive"))
      (node (ref "C51") (pin "2") (pinfunction "2_2") (pintype "passive"))
      (node (ref "C52") (pin "2") (pinfunction "2_2") (pintype "passive"))
      (node (ref "C54") (pin "2") (pinfunction "2_2") (pintype "passive"))
      (node (ref "C55") (pin "2") (pinfunction "2_2") (pintype "passive"))
      (node (ref "C56") (pin "2") (pinfunction "2_2") (pintype "passive"))
      (node (ref "C57") (pin "2") (pinfunction "2_2") (pintype "passive"))
      (node (ref "C58") (pin "1") (pinfunction "1_1") (pintype "passive"))
      (node (ref "C59") (pin "1") (pinfunction "1_1") (pintype "passive"))
      (node (ref "C60") (pin "2") (pinfunction "2_2") (pintype "passive"))
      (node (ref "C61") (pin "2") (pinfunction "2_2") (pintype "passive"))
      (node (ref "C62") (pin "2") (pinfunction "2_2") (pintype "passive"))
      (node (ref "C63") (pin "2") (pinfunction "2_2") (pintype "passive"))
      (node (ref "C64") (pin "2") (pinfunction "2_2") (pintype "passive"))
      (node (ref "C65") (pin "2") (pinfunction "2_2") (pintype "passive"))
      (node (ref "D1") (pin "2") (pinfunction "K_2") (pintype "passive"))
      (node (ref "D3") (pin "2") (pinfunction "K_2") (pintype "passive"))
      (node (ref "D4") (pin "2") (pinfunction "K_2") (pintype "passive"))
      (node (ref "D5") (pin "2") (pinfunction "K_2") (pintype "passive"))
      (node (ref "J5") (pin "9") (pinfunction "9_9") (pintype "passive"))
      (node (ref "J6") (pin "4") (pinfunction "GND_4") (pintype "passive"))
      (node (ref "J6") (pin "5") (pinfunction "NC_5") (pintype "passive"))
      (node (ref "J6") (pin "6") (pinfunction "SHIELD_6") (pintype "passive"))
      (node (ref "R33") (pin "2") (pinfunction "2_2") (pintype "passive"))
      (node (ref "SW1") (pin "3") (pinfunction "3_3") (pintype "passive"))
      (node (ref "SW1") (pin "4") (pinfunction "4_4") (pintype "passive"))
      (node (ref "SW3") (pin "3") (pinfunction "3_3") (pintype "passive"))
      (node (ref "SW3") (pin "4") (pinfunction "4_4") (pintype "passive"))
      (node (ref "U10") (pin "14") (pinfunction "AVSS1_14") (pintype "power_in"))
      (node (ref "U10") (pin "19") (pinfunction "DVSS1_19") (pintype "power_in"))
      (node (ref "U10") (pin "49") (pinfunction "DVSS2_49") (pintype "power_in"))
      (node (ref "U10") (pin "61") (pinfunction "VSSU_61") (pintype "power_in"))
      (node (ref "U10") (pin "68") (pinfunction "AVSS2_68") (pintype "power_in"))
      (node (ref "U11") (pin "4") (pinfunction "GND_4") (pintype "power_in"))
      (node (ref "X1") (pin "2") (pinfunction "GND_2") (pintype "passive"))
      (node (ref "X1") (pin "4") (pinfunction "GND_4") (pintype "passive"))
    )
    (net (code "69") (name "Net-(D1-A)") (class "Default")
      (node (ref "D1") (pin "1") (pinfunction "A_1") (pintype "passive"))
      (node (ref "R27") (pin "1") (pinfunction "1_1") (pintype "passive"))
    )
    (net (code "70") (name "Net-(D2-A)") (class "Default")
      (node (ref "D2") (pin "3") (pinfunction "A_3") (pintype "passive"))
      (node (ref "J6") (pin "1") (pinfunction "Vcc_1") (pintype "passive"))
      (node (ref "R27") (pin "2") (pinfunction "2_2") (pintype "passive"))
      (node (ref "U11") (pin "1") (pinfunction "VCC_1") (pintype "power_in"))
    )
    (net (code "71") (name "Net-(D2-K)") (class "Default")
      (node (ref "D2") (pin "1") (pinfunction "K_1") (pintype "passive"))
      (node (ref "R28") (pin "2") (pinfunction "2_2") (pintype "passive"))
    )
    (net (code "72") (name "Net-(D3-A)") (class "Default")
      (node (ref "D3") (pin "1") (pinfunction "A_1") (pintype "passive"))
      (node (ref "R4") (pin "1") (pinfunction "1_1") (pintype "passive"))
    )
    (net (code "73") (name "Net-(D4-A)") (class "Default")
      (node (ref "D4") (pin "1") (pinfunction "A_1") (pintype "passive"))
      (node (ref "R7") (pin "1") (pinfunction "1_1") (pintype "passive"))
    )
    (net (code "74") (name "Net-(D5-A)") (class "Default")
      (node (ref "D5") (pin "1") (pinfunction "A_1") (pintype "passive"))
      (node (ref "R8") (pin "1") (pinfunction "1_1") (pintype "passive"))
    )
    (net (code "75") (name "Net-(J6-D+)") (class "Default")
      (node (ref "J6") (pin "3") (pinfunction "D+_3") (pintype "passive"))
      (node (ref "R32") (pin "2") (pinfunction "2_2") (pintype "passive"))
      (node (ref "U11") (pin "3") (pinfunction "IO1_3") (pintype "power_in"))
    )
    (net (code "76") (name "Net-(J6-D-)") (class "Default")
      (node (ref "J6") (pin "2") (pinfunction "D-_2") (pintype "passive"))
      (node (ref "R30") (pin "2") (pinfunction "2_2") (pintype "passive"))
      (node (ref "U11") (pin "2") (pinfunction "NC_2") (pintype "power_in"))
      (node (ref "U11") (pin "5") (pinfunction "IO2_5") (pintype "power_in"))
    )
    (net (code "77") (name "Net-(R29-Pad2)") (class "Default")
      (node (ref "R29") (pin "2") (pinfunction "2_2") (pintype "passive"))
      (node (ref "SW2") (pin "3") (pinfunction "3_3") (pintype "passive"))
      (node (ref "SW2") (pin "4") (pinfunction "4_4") (pintype "passive"))
    )
    (net (code "78") (name "Net-(U10-V18)") (class "Default")
      (node (ref "C55") (pin "1") (pinfunction "1_1") (pintype "passive"))
      (node (ref "U10") (pin "67") (pinfunction "V18_67") (pintype "passive"))
    )
    (net (code "79") (name "Net-(U10-VBUS)") (class "Default")
      (node (ref "R26") (pin "2") (pinfunction "2_2") (pintype "passive"))
      (node (ref "U10") (pin "65") (pinfunction "VBUS_65") (pintype "power_in"))
    )
    (net (code "80") (name "Net-(U10-VCORE)") (class "Default")
      (node (ref "C56") (pin "1") (pinfunction "1_1") (pintype "passive"))
      (node (ref "U10") (pin "20") (pinfunction "VCORE_20") (pintype "passive"))
    )
    (net (code "81") (name "VCC3V3") (class "Default")
      (node (ref "C48") (pin "1") (pinfunction "1_1") (pintype "passive"))
      (node (ref "C50") (pin "1") (pinfunction "1_1") (pintype "passive"))
      (node (ref "C51") (pin "1") (pinfunction "1_1") (pintype "passive"))
      (node (ref "C52") (pin "1") (pinfunction "1_1") (pintype "passive"))
      (node (ref "C54") (pin "1") (pinfunction "1_1") (pintype "passive"))
      (node (ref "J5") (pin "4") (pinfunction "4_4") (pintype "passive"))
      (node (ref "R20") (pin "2") (pinfunction "2_2") (pintype "passive"))
      (node (ref "R21") (pin "2") (pinfunction "2_2") (pintype "passive"))
      (node (ref "R22") (pin "2") (pinfunction "2_2") (pintype "passive"))
      (node (ref "R23") (pin "2") (pinfunction "2_2") (pintype "passive"))
      (node (ref "R24") (pin "2") (pinfunction "2_2") (pintype "passive"))
      (node (ref "R25") (pin "2") (pinfunction "2_2") (pintype "passive"))
      (node (ref "R3") (pin "2") (pinfunction "2_2") (pintype "passive"))
      (node (ref "U10") (pin "18") (pinfunction "DVCC1_18") (pintype "power_in"))
      (node (ref "U10") (pin "50") (pinfunction "DVCC2_50") (pintype "power_in"))
    )
    (net (code "82") (name "unconnected-(J5-Pad2)") (class "Default")
      (node (ref "J5") (pin "2") (pinfunction "2_2") (pintype "passive"))
    )
    (net (code "83") (name "unconnected-(J5-Pad6)") (class "Default")
      (node (ref "J5") (pin "6") (pinfunction "6_6") (pintype "passive"))
    )
    (net (code "84") (name "unconnected-(J5-Pad10)") (class "Default")
      (node (ref "J5") (pin "10") (pinfunction "10_10") (pintype "passive"))
    )
    (net (code "85") (name "unconnected-(J5-Pad12)") (class "Default")
      (node (ref "J5") (pin "12") (pinfunction "12_12") (pintype "passive"))
    )
    (net (code "86") (name "unconnected-(J5-Pad13)") (class "Default")
      (node (ref "J5") (pin "13") (pinfunction "13_13") (pintype "passive"))
    )
    (net (code "87") (name "unconnected-(J5-Pad14)") (class "Default")
      (node (ref "J5") (pin "14") (pinfunction "14_14") (pintype "passive"))
    )
    (net (code "88") (name "unconnected-(U10-P4.3{slash}PM_UCB1CLK{slash}PM_UCA1STE-Pad48)") (class "Default")
      (node (ref "U10") (pin "48") (pinfunction "P4.3/PM_UCB1CLK/PM_UCA1STE_48") (pintype "bidirectional"))
    )
    (net (code "89") (name "unconnected-(U10-P8.0-Pad15)") (class "Default")
      (node (ref "U10") (pin "15") (pinfunction "P8.0_15") (pintype "bidirectional"))
    )
    (net (code "90") (name "unconnected-(U10-P8.1-Pad16)") (class "Default")
      (node (ref "U10") (pin "16") (pinfunction "P8.1_16") (pintype "bidirectional"))
    )
    (net (code "91") (name "unconnected-(U10-P8.2-Pad17)") (class "Default")
      (node (ref "U10") (pin "17") (pinfunction "P8.2_17") (pintype "bidirectional"))
    )
  )
)
